# control.net
KiCad netlist of a schematic drawn in EAGLE
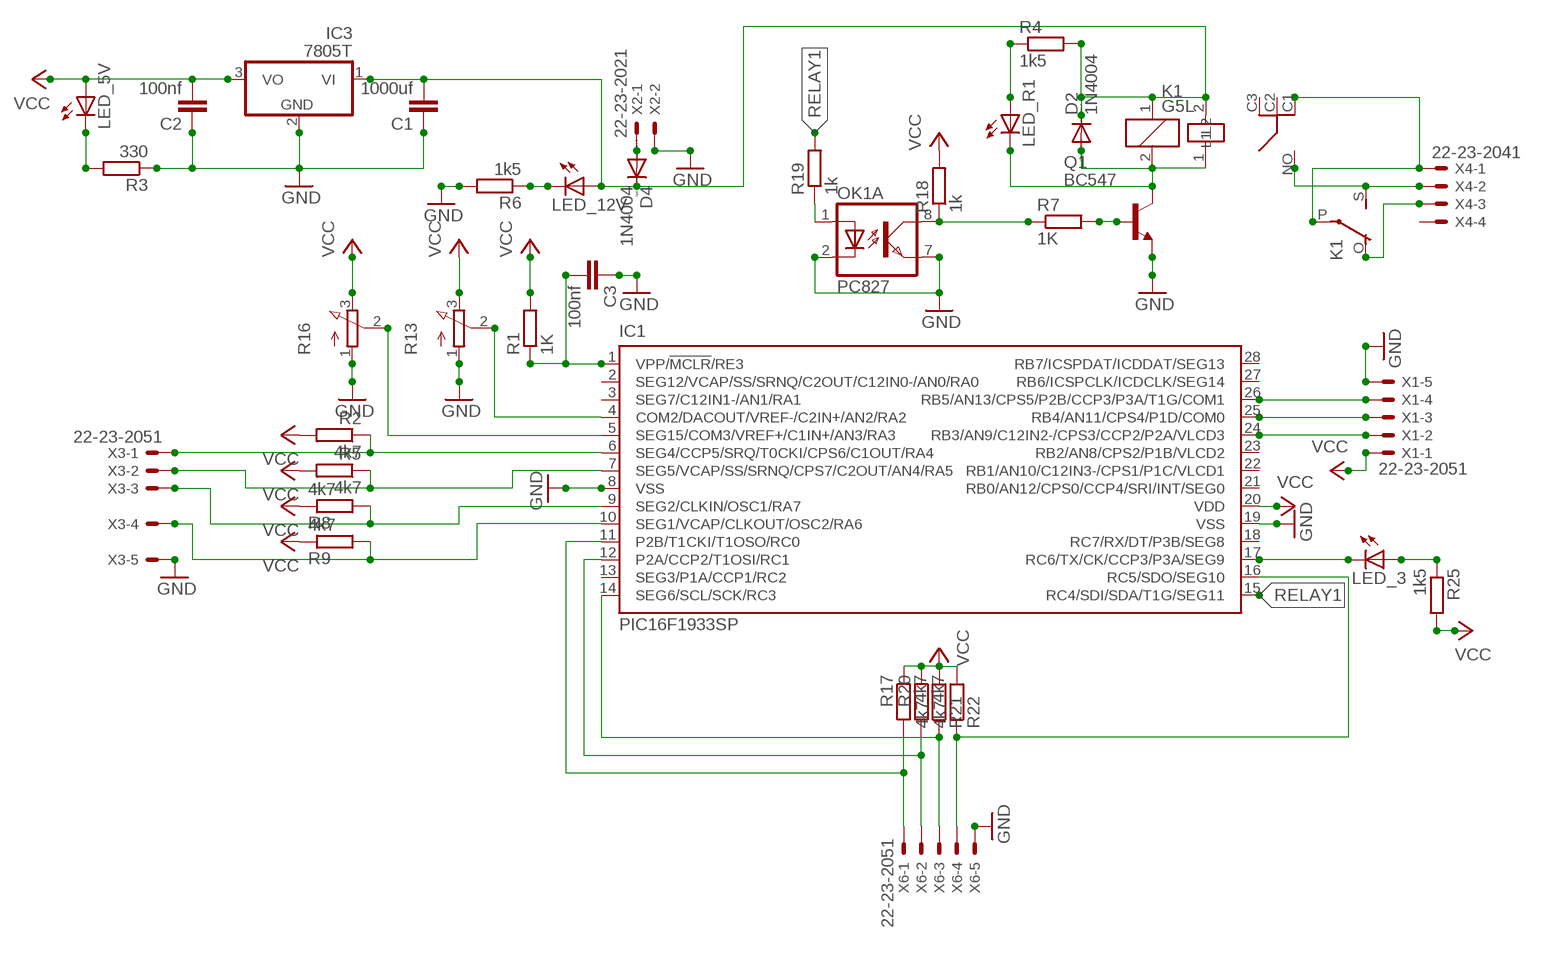
[diagram p0: schematic, sheet 1]

(export (version "E")
  (design (tool "Eeschema 10.0.6"))
  (components
    (comp (ref "C1")
      (value "1000uf")
      (footprint "eagle-import:C5B2.5")
      (libsource (lib "eagle-import") (part "C5/2.5"))
    )
    (comp (ref "C2")
      (value "100nf")
      (footprint "eagle-import:C2.5-6")
      (libsource (lib "eagle-import") (part "C2.5/6"))
    )
    (comp (ref "C3")
      (value "100nf")
      (footprint "eagle-import:C2.5-6")
      (libsource (lib "eagle-import") (part "C2.5/6"))
    )
    (comp (ref "D2")
      (value "1N4004")
      (footprint "eagle-import:DO41-10")
      (libsource (lib "eagle-import") (part "1N4004"))
    )
    (comp (ref "D4")
      (value "1N4004")
      (footprint "eagle-import:DO41-10")
      (libsource (lib "eagle-import") (part "1N4004"))
    )
    (comp (ref "IC1")
      (value "PIC16F1933SP")
      (footprint "eagle-import:DIL28-3")
      (fields (field (name "MPN") "PIC16F1933-I/SP"))
      (libsource (lib "eagle-import") (part "PIC16F19SP33"))
    )
    (comp (ref "IC3")
      (value "7805T")
      (footprint "eagle-import:TO220H")
      (libsource (lib "eagle-import") (part "78T05"))
    )
    (comp (ref "K1")
      (value "G5L")
      (footprint "eagle-import:G5LE")
      (libsource (lib "eagle-import") (part "G5L"))
    )
    (comp (ref "LED_3")
      (value "LED3MM")
      (footprint "eagle-import:LED3MM")
      (libsource (lib "eagle-import") (part "LED3MM"))
    )
    (comp (ref "LED_5V")
      (value "LED3MM")
      (footprint "eagle-import:LED3MM")
      (libsource (lib "eagle-import") (part "LED3MM"))
    )
    (comp (ref "LED_12V")
      (value "LED3MM")
      (footprint "eagle-import:LED3MM")
      (libsource (lib "eagle-import") (part "LED3MM"))
    )
    (comp (ref "LED_R1")
      (value "LED3MM")
      (footprint "eagle-import:LED3MM")
      (libsource (lib "eagle-import") (part "LED3MM"))
    )
    (comp (ref "OK1")
      (value "PC827")
      (footprint "eagle-import:DIL08")
      (libsource (lib "eagle-import") (part "PC827"))
    )
    (comp (ref "Q1")
      (value "BC547")
      (footprint "eagle-import:TO92-EBC")
      (libsource (lib "eagle-import") (part "BC548"))
    )
    (comp (ref "R1")
      (value "1K")
      (footprint "eagle-import:0207_10")
      (libsource (lib "eagle-import") (part "R-EU_0207/10"))
    )
    (comp (ref "R2")
      (value "4k7")
      (footprint "eagle-import:0207_10")
      (libsource (lib "eagle-import") (part "R-EU_0207/10"))
    )
    (comp (ref "R3")
      (value "330")
      (footprint "eagle-import:0207_10")
      (libsource (lib "eagle-import") (part "R-EU_0207/10"))
    )
    (comp (ref "R4")
      (value "1k5")
      (footprint "eagle-import:0207_10")
      (libsource (lib "eagle-import") (part "R-EU_0207/10"))
    )
    (comp (ref "R5")
      (value "4k7")
      (footprint "eagle-import:0207_10")
      (libsource (lib "eagle-import") (part "R-EU_0207/10"))
    )
    (comp (ref "R6")
      (value "1k5")
      (footprint "eagle-import:0207_10")
      (libsource (lib "eagle-import") (part "R-EU_0207/10"))
    )
    (comp (ref "R7")
      (value "1K")
      (footprint "eagle-import:0207_10")
      (libsource (lib "eagle-import") (part "R-EU_0207/10"))
    )
    (comp (ref "R8")
      (value "4k7")
      (footprint "eagle-import:0207_10")
      (libsource (lib "eagle-import") (part "R-EU_0207/10"))
    )
    (comp (ref "R9")
      (value "4k7")
      (footprint "eagle-import:0207_10")
      (libsource (lib "eagle-import") (part "R-EU_0207/10"))
    )
    (comp (ref "R13")
      (value "3RP/1610N")
      (footprint "eagle-import:3RP_1610N")
      (libsource (lib "eagle-import") (part "3RP/1610N"))
    )
    (comp (ref "R16")
      (value "3RP/1610N")
      (footprint "eagle-import:3RP_1610N")
      (libsource (lib "eagle-import") (part "3RP/1610N"))
    )
    (comp (ref "R17")
      (value "4k7")
      (footprint "eagle-import:0207_10")
      (libsource (lib "eagle-import") (part "R-EU_0207/10"))
    )
    (comp (ref "R18")
      (value "1k")
      (footprint "eagle-import:0207_10")
      (libsource (lib "eagle-import") (part "R-EU_0207/10"))
    )
    (comp (ref "R19")
      (value "1k")
      (footprint "eagle-import:0207_10")
      (libsource (lib "eagle-import") (part "R-EU_0207/10"))
    )
    (comp (ref "R20")
      (value "4k7")
      (footprint "eagle-import:0207_10")
      (libsource (lib "eagle-import") (part "R-EU_0207/10"))
    )
    (comp (ref "R21")
      (value "4k7")
      (footprint "eagle-import:0207_10")
      (libsource (lib "eagle-import") (part "R-EU_0207/10"))
    )
    (comp (ref "R22")
      (value "4k7")
      (footprint "eagle-import:0207_10")
      (libsource (lib "eagle-import") (part "R-EU_0207/10"))
    )
    (comp (ref "R25")
      (value "1k5")
      (footprint "eagle-import:0207_10")
      (libsource (lib "eagle-import") (part "R-EU_0207/10"))
    )
    (comp (ref "U$1")
      (value "RL703")
      (footprint "eagle-import:RL703")
      (libsource (lib "eagle-import") (part "RL703"))
    )
    (comp (ref "X1")
      (value "22-23-2051")
      (footprint "eagle-import:22-23-2051")
      (fields (field (name "MF") "MOLEX"))
      (libsource (lib "eagle-import") (part "22-23-2051"))
    )
    (comp (ref "X2")
      (value "22-23-2021")
      (footprint "eagle-import:22-23-2021")
      (fields (field (name "MF") "MOLEX"))
      (libsource (lib "eagle-import") (part "22-23-2021"))
    )
    (comp (ref "X3")
      (value "22-23-2051")
      (footprint "eagle-import:22-23-2051")
      (fields (field (name "MF") "MOLEX"))
      (libsource (lib "eagle-import") (part "22-23-2051"))
    )
    (comp (ref "X4")
      (value "22-23-2041")
      (footprint "eagle-import:22-23-2041")
      (fields (field (name "MF") "MOLEX"))
      (libsource (lib "eagle-import") (part "22-23-2041"))
    )
    (comp (ref "X6")
      (value "22-23-2051")
      (footprint "eagle-import:22-23-2051")
      (fields (field (name "MF") "MOLEX"))
      (libsource (lib "eagle-import") (part "22-23-2051"))
    )
  )
  (nets
    (net (code "1") (name "GND") (class "Default")
      (node (ref "C1") (pin "1") (pinfunction "1_1") (pintype "passive"))
      (node (ref "C2") (pin "1") (pinfunction "1_1") (pintype "passive"))
      (node (ref "C3") (pin "1") (pinfunction "1_1") (pintype "passive"))
      (node (ref "IC1") (pin "19") (pinfunction "VSS_19") (pintype "power_in"))
      (node (ref "IC1") (pin "8") (pinfunction "VSS_8") (pintype "power_in"))
      (node (ref "IC3") (pin "2") (pinfunction "GND_2") (pintype "passive"))
      (node (ref "OK1") (pin "2") (pinfunction "C_2") (pintype "passive"))
      (node (ref "OK1") (pin "7") (pinfunction "EMIT_7") (pintype "passive"))
      (node (ref "Q1") (pin "E") (pinfunction "E_E") (pintype "passive"))
      (node (ref "R13") (pin "1") (pinfunction "A_1") (pintype "passive"))
      (node (ref "R16") (pin "1") (pinfunction "A_1") (pintype "passive"))
      (node (ref "R3") (pin "1") (pinfunction "1_1") (pintype "passive"))
      (node (ref "R6") (pin "2") (pinfunction "2_2") (pintype "passive"))
      (node (ref "X1") (pin "5") (pinfunction "S_5") (pintype "passive"))
      (node (ref "X2") (pin "2") (pinfunction "S_2") (pintype "passive"))
      (node (ref "X3") (pin "5") (pinfunction "S_5") (pintype "passive"))
      (node (ref "X6") (pin "5") (pinfunction "S_5") (pintype "passive"))
    )
    (net (code "2") (name "Net-(IC1-COM2{slash}DACOUT{slash}VREF-{slash}C2IN+{slash}AN2{slash}RA2)") (class "Default")
      (node (ref "IC1") (pin "4") (pinfunction "COM2/DACOUT/VREF-/C2IN+/AN2/RA2_4") (pintype "bidirectional"))
      (node (ref "R13") (pin "2") (pinfunction "S_2") (pintype "passive"))
    )
    (net (code "3") (name "Net-(IC1-P2A{slash}CCP2{slash}T1OSI{slash}RC1)") (class "Default")
      (node (ref "IC1") (pin "12") (pinfunction "P2A/CCP2/T1OSI/RC1_12") (pintype "bidirectional"))
      (node (ref "R20") (pin "2") (pinfunction "2_2") (pintype "passive"))
      (node (ref "X6") (pin "2") (pinfunction "S_2") (pintype "passive"))
    )
    (net (code "4") (name "Net-(IC1-P2B{slash}T1CKI{slash}T1OSO{slash}RC0)") (class "Default")
      (node (ref "IC1") (pin "11") (pinfunction "P2B/T1CKI/T1OSO/RC0_11") (pintype "bidirectional"))
      (node (ref "R17") (pin "2") (pinfunction "2_2") (pintype "passive"))
      (node (ref "X6") (pin "1") (pinfunction "S_1") (pintype "passive"))
    )
    (net (code "5") (name "Net-(IC1-RB3{slash}AN9{slash}C12IN2-{slash}CPS3{slash}CCP2{slash}P2A{slash}VLCD3)") (class "Default")
      (node (ref "IC1") (pin "24") (pinfunction "RB3/AN9/C12IN2-/CPS3/CCP2/P2A/VLCD3_24") (pintype "bidirectional"))
      (node (ref "X1") (pin "2") (pinfunction "S_2") (pintype "passive"))
    )
    (net (code "6") (name "Net-(IC1-RB4{slash}AN11{slash}CPS4{slash}P1D{slash}COM0)") (class "Default")
      (node (ref "IC1") (pin "25") (pinfunction "RB4/AN11/CPS4/P1D/COM0_25") (pintype "bidirectional"))
      (node (ref "X1") (pin "3") (pinfunction "S_3") (pintype "passive"))
    )
    (net (code "7") (name "Net-(IC1-RB5{slash}AN13{slash}CPS5{slash}P2B{slash}CCP3{slash}P3A{slash}T1G{slash}COM1)") (class "Default")
      (node (ref "IC1") (pin "26") (pinfunction "RB5/AN13/CPS5/P2B/CCP3/P3A/T1G/COM1_26") (pintype "bidirectional"))
      (node (ref "X1") (pin "4") (pinfunction "S_4") (pintype "passive"))
    )
    (net (code "8") (name "Net-(IC1-RC5{slash}SDO{slash}SEG10)") (class "Default")
      (node (ref "IC1") (pin "16") (pinfunction "RC5/SDO/SEG10_16") (pintype "bidirectional"))
      (node (ref "R22") (pin "1") (pinfunction "1_1") (pintype "passive"))
      (node (ref "X6") (pin "4") (pinfunction "S_4") (pintype "passive"))
    )
    (net (code "9") (name "Net-(IC1-RC6{slash}TX{slash}CK{slash}CCP3{slash}P3A{slash}SEG9)") (class "Default")
      (node (ref "IC1") (pin "17") (pinfunction "RC6/TX/CK/CCP3/P3A/SEG9_17") (pintype "bidirectional"))
      (node (ref "LED_3") (pin "K") (pinfunction "C_K") (pintype "passive"))
    )
    (net (code "10") (name "Net-(IC1-SEG1{slash}VCAP{slash}CLKOUT{slash}OSC2{slash}RA6)") (class "Default")
      (node (ref "IC1") (pin "10") (pinfunction "SEG1/VCAP/CLKOUT/OSC2/RA6_10") (pintype "bidirectional"))
      (node (ref "R9") (pin "2") (pinfunction "2_2") (pintype "passive"))
      (node (ref "X3") (pin "4") (pinfunction "S_4") (pintype "passive"))
    )
    (net (code "11") (name "Net-(IC1-SEG2{slash}CLKIN{slash}OSC1{slash}RA7)") (class "Default")
      (node (ref "IC1") (pin "9") (pinfunction "SEG2/CLKIN/OSC1/RA7_9") (pintype "bidirectional"))
      (node (ref "R8") (pin "2") (pinfunction "2_2") (pintype "passive"))
      (node (ref "X3") (pin "3") (pinfunction "S_3") (pintype "passive"))
    )
    (net (code "12") (name "Net-(IC1-SEG4{slash}CCP5{slash}SRQ{slash}T0CKI{slash}CPS6{slash}C1OUT{slash}RA4)") (class "Default")
      (node (ref "IC1") (pin "6") (pinfunction "SEG4/CCP5/SRQ/T0CKI/CPS6/C1OUT/RA4_6") (pintype "bidirectional"))
      (node (ref "R2") (pin "1") (pinfunction "1_1") (pintype "passive"))
      (node (ref "X3") (pin "1") (pinfunction "S_1") (pintype "passive"))
    )
    (net (code "13") (name "Net-(IC1-SEG5{slash}VCAP{slash}SS{slash}SRNQ{slash}CPS7{slash}C2OUT{slash}AN4{slash}RA5)") (class "Default")
      (node (ref "IC1") (pin "7") (pinfunction "SEG5/VCAP/SS/SRNQ/CPS7/C2OUT/AN4/RA5_7") (pintype "bidirectional"))
      (node (ref "R5") (pin "1") (pinfunction "1_1") (pintype "passive"))
      (node (ref "X3") (pin "2") (pinfunction "S_2") (pintype "passive"))
    )
    (net (code "14") (name "Net-(IC1-SEG6{slash}SCL{slash}SCK{slash}RC3)") (class "Default")
      (node (ref "IC1") (pin "14") (pinfunction "SEG6/SCL/SCK/RC3_14") (pintype "bidirectional"))
      (node (ref "R21") (pin "1") (pinfunction "1_1") (pintype "passive"))
      (node (ref "X6") (pin "3") (pinfunction "S_3") (pintype "passive"))
    )
    (net (code "15") (name "Net-(IC1-SEG15{slash}COM3{slash}VREF+{slash}C1IN+{slash}AN3{slash}RA3)") (class "Default")
      (node (ref "IC1") (pin "5") (pinfunction "SEG15/COM3/VREF+/C1IN+/AN3/RA3_5") (pintype "bidirectional"))
      (node (ref "R16") (pin "2") (pinfunction "S_2") (pintype "passive"))
    )
    (net (code "16") (name "Net-(IC1-VPP{slash}~{MCLR}{slash}RE3)") (class "Default")
      (node (ref "C3") (pin "2") (pinfunction "2_2") (pintype "passive"))
      (node (ref "IC1") (pin "1") (pinfunction "VPP/~{MCLR}/RE3_1") (pintype "input"))
      (node (ref "R1") (pin "1") (pinfunction "1_1") (pintype "passive"))
    )
    (net (code "17") (name "Net-(IC3-VI)") (class "Default")
      (node (ref "C1") (pin "2") (pinfunction "2_2") (pintype "passive"))
      (node (ref "D2") (pin "C") (pinfunction "C_C") (pintype "passive"))
      (node (ref "D4") (pin "C") (pinfunction "C_C") (pintype "passive"))
      (node (ref "IC3") (pin "1") (pinfunction "VI_1") (pintype "input"))
      (node (ref "K1") (pin "1") (pinfunction "1_1") (pintype "passive"))
      (node (ref "LED_12V") (pin "A") (pinfunction "A_A") (pintype "passive"))
      (node (ref "R4") (pin "2") (pinfunction "2_2") (pintype "passive"))
      (node (ref "U$1") (pin "2") (pinfunction "L1_2") (pintype "bidirectional"))
    )
    (net (code "18") (name "Net-(LED_3-PadA)") (class "Default")
      (node (ref "LED_3") (pin "A") (pinfunction "A_A") (pintype "passive"))
      (node (ref "R25") (pin "1") (pinfunction "1_1") (pintype "passive"))
    )
    (net (code "19") (name "Net-(LED_5V-C)") (class "Default")
      (node (ref "LED_5V") (pin "K") (pinfunction "C_K") (pintype "passive"))
      (node (ref "R3") (pin "2") (pinfunction "2_2") (pintype "passive"))
    )
    (net (code "20") (name "Net-(LED_12V-C)") (class "Default")
      (node (ref "LED_12V") (pin "K") (pinfunction "C_K") (pintype "passive"))
      (node (ref "R6") (pin "1") (pinfunction "1_1") (pintype "passive"))
    )
    (net (code "21") (name "Net-(LED_R1-C)") (class "Default")
      (node (ref "D2") (pin "A") (pinfunction "A_A") (pintype "passive"))
      (node (ref "K1") (pin "2") (pinfunction "2_2") (pintype "passive"))
      (node (ref "LED_R1") (pin "K") (pinfunction "C_K") (pintype "passive"))
      (node (ref "Q1") (pin "C") (pinfunction "C_C") (pintype "passive"))
      (node (ref "U$1") (pin "1") (pinfunction "L2_1") (pintype "bidirectional"))
    )
    (net (code "22") (name "Net-(LED_R1-PadA)") (class "Default")
      (node (ref "LED_R1") (pin "A") (pinfunction "A_A") (pintype "passive"))
      (node (ref "R4") (pin "1") (pinfunction "1_1") (pintype "passive"))
    )
    (net (code "23") (name "Net-(OK1A-A)") (class "Default")
      (node (ref "OK1") (pin "1") (pinfunction "A_1") (pintype "passive"))
      (node (ref "R19") (pin "1") (pinfunction "1_1") (pintype "passive"))
    )
    (net (code "24") (name "Net-(OK1A-COL)") (class "Default")
      (node (ref "OK1") (pin "8") (pinfunction "COL_8") (pintype "passive"))
      (node (ref "R18") (pin "1") (pinfunction "1_1") (pintype "passive"))
      (node (ref "R7") (pin "1") (pinfunction "1_1") (pintype "passive"))
    )
    (net (code "25") (name "Net-(Q1-PadB)") (class "Default")
      (node (ref "Q1") (pin "B") (pinfunction "B_B") (pintype "passive"))
      (node (ref "R7") (pin "2") (pinfunction "2_2") (pintype "passive"))
    )
    (net (code "26") (name "Net-(X2A-S)") (class "Default")
      (node (ref "D4") (pin "A") (pinfunction "A_A") (pintype "passive"))
      (node (ref "X2") (pin "1") (pinfunction "S_1") (pintype "passive"))
    )
    (net (code "27") (name "Net-(X4A-S)") (class "Default")
      (node (ref "K1") (pin "P") (pinfunction "P_P") (pintype "passive"))
      (node (ref "U$1") (pin "C1") (pinfunction "C1_C1") (pintype "bidirectional"))
      (node (ref "X4") (pin "1") (pinfunction "S_1") (pintype "passive"))
    )
    (net (code "28") (name "Net-(X4B-S)") (class "Default")
      (node (ref "K1") (pin "S") (pinfunction "S_S") (pintype "passive"))
      (node (ref "U$1") (pin "NO") (pinfunction "NO_NO") (pintype "bidirectional"))
      (node (ref "X4") (pin "2") (pinfunction "S_2") (pintype "passive"))
    )
    (net (code "29") (name "Net-(X4C-S)") (class "Default")
      (node (ref "K1") (pin "O") (pinfunction "O_O") (pintype "passive"))
      (node (ref "X4") (pin "3") (pinfunction "S_3") (pintype "passive"))
    )
    (net (code "30") (name "RELAY1") (class "Default")
      (node (ref "IC1") (pin "15") (pinfunction "RC4/SDI/SDA/T1G/SEG11_15") (pintype "bidirectional"))
      (node (ref "R19") (pin "2") (pinfunction "2_2") (pintype "passive"))
    )
    (net (code "31") (name "VCC") (class "Default")
      (node (ref "C2") (pin "2") (pinfunction "2_2") (pintype "passive"))
      (node (ref "IC1") (pin "20") (pinfunction "VDD_20") (pintype "power_in"))
      (node (ref "IC3") (pin "3") (pinfunction "VO_3") (pintype "passive"))
      (node (ref "LED_5V") (pin "A") (pinfunction "A_A") (pintype "passive"))
      (node (ref "R1") (pin "2") (pinfunction "2_2") (pintype "passive"))
      (node (ref "R13") (pin "3") (pinfunction "E_3") (pintype "passive"))
      (node (ref "R16") (pin "3") (pinfunction "E_3") (pintype "passive"))
      (node (ref "R17") (pin "1") (pinfunction "1_1") (pintype "passive"))
      (node (ref "R18") (pin "2") (pinfunction "2_2") (pintype "passive"))
      (node (ref "R2") (pin "2") (pinfunction "2_2") (pintype "passive"))
      (node (ref "R20") (pin "1") (pinfunction "1_1") (pintype "passive"))
      (node (ref "R21") (pin "2") (pinfunction "2_2") (pintype "passive"))
      (node (ref "R22") (pin "2") (pinfunction "2_2") (pintype "passive"))
      (node (ref "R25") (pin "2") (pinfunction "2_2") (pintype "passive"))
      (node (ref "R5") (pin "2") (pinfunction "2_2") (pintype "passive"))
      (node (ref "R8") (pin "1") (pinfunction "1_1") (pintype "passive"))
      (node (ref "R9") (pin "1") (pinfunction "1_1") (pintype "passive"))
      (node (ref "X1") (pin "1") (pinfunction "S_1") (pintype "passive"))
    )
    (net (code "32") (name "unconnected-(IC1-RB0{slash}AN12{slash}CPS0{slash}CCP4{slash}SRI{slash}INT{slash}SEG0-Pad21)") (class "Default")
      (node (ref "IC1") (pin "21") (pinfunction "RB0/AN12/CPS0/CCP4/SRI/INT/SEG0_21") (pintype "bidirectional"))
    )
    (net (code "33") (name "unconnected-(IC1-RB1{slash}AN10{slash}C12IN3-{slash}CPS1{slash}P1C{slash}VLCD1-Pad22)") (class "Default")
      (node (ref "IC1") (pin "22") (pinfunction "RB1/AN10/C12IN3-/CPS1/P1C/VLCD1_22") (pintype "bidirectional"))
    )
    (net (code "34") (name "unconnected-(IC1-RB2{slash}AN8{slash}CPS2{slash}P1B{slash}VLCD2-Pad23)") (class "Default")
      (node (ref "IC1") (pin "23") (pinfunction "RB2/AN8/CPS2/P1B/VLCD2_23") (pintype "bidirectional"))
    )
    (net (code "35") (name "unconnected-(IC1-RB6{slash}ICSPCLK{slash}ICDCLK{slash}SEG14-Pad27)") (class "Default")
      (node (ref "IC1") (pin "27") (pinfunction "RB6/ICSPCLK/ICDCLK/SEG14_27") (pintype "bidirectional"))
    )
    (net (code "36") (name "unconnected-(IC1-RB7{slash}ICSPDAT{slash}ICDDAT{slash}SEG13-Pad28)") (class "Default")
      (node (ref "IC1") (pin "28") (pinfunction "RB7/ICSPDAT/ICDDAT/SEG13_28") (pintype "bidirectional"))
    )
    (net (code "37") (name "unconnected-(IC1-RC7{slash}RX{slash}DT{slash}P3B{slash}SEG8-Pad18)") (class "Default")
      (node (ref "IC1") (pin "18") (pinfunction "RC7/RX/DT/P3B/SEG8_18") (pintype "bidirectional"))
    )
    (net (code "38") (name "unconnected-(IC1-SEG3{slash}P1A{slash}CCP1{slash}RC2-Pad13)") (class "Default")
      (node (ref "IC1") (pin "13") (pinfunction "SEG3/P1A/CCP1/RC2_13") (pintype "bidirectional"))
    )
    (net (code "39") (name "unconnected-(IC1-SEG7{slash}C12IN1-{slash}AN1{slash}RA1-Pad3)") (class "Default")
      (node (ref "IC1") (pin "3") (pinfunction "SEG7/C12IN1-/AN1/RA1_3") (pintype "bidirectional"))
    )
    (net (code "40") (name "unconnected-(IC1-SEG12{slash}VCAP{slash}SS{slash}SRNQ{slash}C2OUT{slash}C12IN0-{slash}AN0{slash}RA0-Pad2)") (class "Default")
      (node (ref "IC1") (pin "2") (pinfunction "SEG12/VCAP/SS/SRNQ/C2OUT/C12IN0-/AN0/RA0_2") (pintype "bidirectional"))
    )
    (net (code "41") (name "unconnected-(U$1-PadC2)") (class "Default")
      (node (ref "U$1") (pin "C2") (pinfunction "C2_C2") (pintype "bidirectional"))
    )
    (net (code "42") (name "unconnected-(U$1-PadC3)") (class "Default")
      (node (ref "U$1") (pin "C3") (pinfunction "C3_C3") (pintype "bidirectional"))
    )
    (net (code "43") (name "unconnected-(X4D-S-Pad4)") (class "Default")
      (node (ref "X4") (pin "4") (pinfunction "S_4") (pintype "passive"))
    )
  )
)
